# master-sim800-esp32-30pin.net
KiCad netlist of a schematic drawn in EAGLE
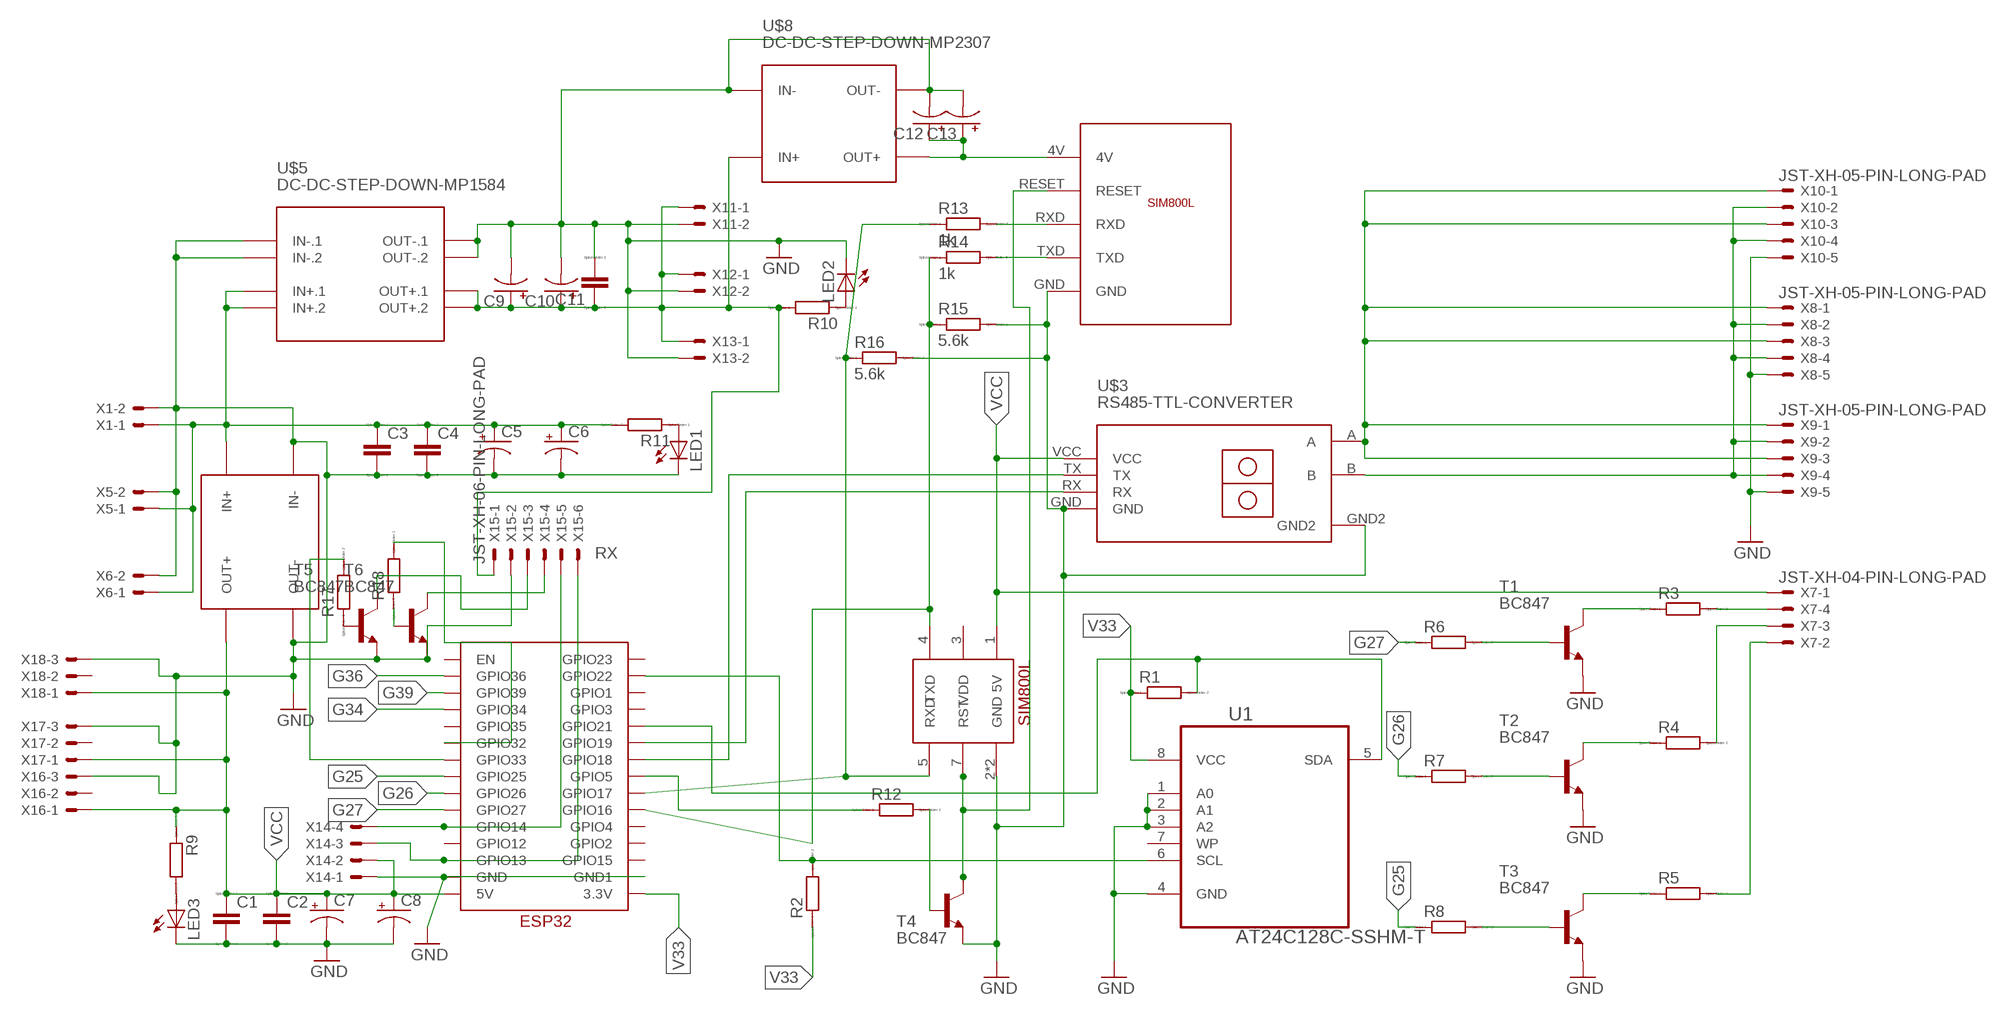
[diagram p0: schematic, sheet 1]

(export (version "E")
  (design (tool "Eeschema 10.0.6"))
  (components
    (comp (ref "C1") (value "C") (footprint "eagle-import:C0805") (libsource (lib "eagle-import") (part "C")))
    (comp (ref "C2") (value "C") (footprint "eagle-import:C0805") (libsource (lib "eagle-import") (part "C")))
    (comp (ref "C3") (value "C") (footprint "eagle-import:C0805") (libsource (lib "eagle-import") (part "C")))
    (comp (ref "C4") (value "C") (footprint "eagle-import:C0805") (libsource (lib "eagle-import") (part "C")))
    (comp (ref "C5")
      (value "CPOL-USE5-8.5")
      (footprint "eagle-import:E5-8,5")
      (libsource (lib "eagle-import") (part "CPOL-USE5-8.5"))
    )
    (comp (ref "C6")
      (value "CPOL-USE5-8.5")
      (footprint "eagle-import:E5-8,5")
      (libsource (lib "eagle-import") (part "CPOL-USE5-8.5"))
    )
    (comp (ref "C7")
      (value "CPOL-USE5-8.5")
      (footprint "eagle-import:E5-8,5")
      (libsource (lib "eagle-import") (part "CPOL-USE5-8.5"))
    )
    (comp (ref "C8")
      (value "CPOL-USE5-8.5")
      (footprint "eagle-import:E5-8,5")
      (libsource (lib "eagle-import") (part "CPOL-USE5-8.5"))
    )
    (comp (ref "C9")
      (value "CPOL-USE5-6")
      (footprint "eagle-import:E5-6")
      (libsource (lib "eagle-import") (part "CPOL-USE5-6"))
    )
    (comp (ref "C10")
      (value "CPOL-USE5-6")
      (footprint "eagle-import:E5-6")
      (libsource (lib "eagle-import") (part "CPOL-USE5-6"))
    )
    (comp (ref "C11")
      (value "C")
      (footprint "eagle-import:C0805")
      (libsource (lib "eagle-import") (part "C"))
    )
    (comp (ref "C12")
      (value "CPOL-USE5-8.5")
      (footprint "eagle-import:E5-8,5")
      (libsource (lib "eagle-import") (part "CPOL-USE5-8.5"))
    )
    (comp (ref "C13")
      (value "CPOL-USE5-8.5")
      (footprint "eagle-import:E5-8,5")
      (libsource (lib "eagle-import") (part "CPOL-USE5-8.5"))
    )
    (comp (ref "LED1")
      (value "LEDCHIPLED_1206")
      (footprint "eagle-import:CHIPLED_1206")
      (libsource (lib "eagle-import") (part "LEDCHIPLED_1206"))
    )
    (comp (ref "LED2")
      (value "LEDCHIPLED_1206")
      (footprint "eagle-import:CHIPLED_1206")
      (libsource (lib "eagle-import") (part "LEDCHIPLED_1206"))
    )
    (comp (ref "LED3")
      (value "LEDCHIPLED_1206")
      (footprint "eagle-import:CHIPLED_1206")
      (libsource (lib "eagle-import") (part "LEDCHIPLED_1206"))
    )
    (comp (ref "R1")
      (value "RR1206")
      (footprint "eagle-import:R1206")
      (libsource (lib "eagle-import") (part "RR1206"))
    )
    (comp (ref "R2")
      (value "RR1206")
      (footprint "eagle-import:R1206")
      (libsource (lib "eagle-import") (part "RR1206"))
    )
    (comp (ref "R3")
      (value "RR1206")
      (footprint "eagle-import:R1206")
      (libsource (lib "eagle-import") (part "RR1206"))
    )
    (comp (ref "R4")
      (value "RR1206")
      (footprint "eagle-import:R1206")
      (libsource (lib "eagle-import") (part "RR1206"))
    )
    (comp (ref "R5")
      (value "RR1206")
      (footprint "eagle-import:R1206")
      (libsource (lib "eagle-import") (part "RR1206"))
    )
    (comp (ref "R6")
      (value "RR1206")
      (footprint "eagle-import:R1206")
      (libsource (lib "eagle-import") (part "RR1206"))
    )
    (comp (ref "R7")
      (value "RR1206")
      (footprint "eagle-import:R1206")
      (libsource (lib "eagle-import") (part "RR1206"))
    )
    (comp (ref "R8")
      (value "RR1206")
      (footprint "eagle-import:R1206")
      (libsource (lib "eagle-import") (part "RR1206"))
    )
    (comp (ref "R9")
      (value "RR1206")
      (footprint "eagle-import:R1206")
      (libsource (lib "eagle-import") (part "RR1206"))
    )
    (comp (ref "R10")
      (value "RR1206")
      (footprint "eagle-import:R1206")
      (libsource (lib "eagle-import") (part "RR1206"))
    )
    (comp (ref "R11")
      (value "RR1206")
      (footprint "eagle-import:R1206")
      (libsource (lib "eagle-import") (part "RR1206"))
    )
    (comp (ref "R12")
      (value "RR1206")
      (footprint "eagle-import:R1206")
      (libsource (lib "eagle-import") (part "RR1206"))
    )
    (comp (ref "R13")
      (value "1k")
      (footprint "eagle-import:R1206")
      (libsource (lib "eagle-import") (part "RR1206"))
    )
    (comp (ref "R14")
      (value "1k")
      (footprint "eagle-import:R1206")
      (libsource (lib "eagle-import") (part "RR1206"))
    )
    (comp (ref "R15")
      (value "5.6k")
      (footprint "eagle-import:R1206")
      (libsource (lib "eagle-import") (part "RR1206"))
    )
    (comp (ref "R16")
      (value "5.6k")
      (footprint "eagle-import:R1206")
      (libsource (lib "eagle-import") (part "RR1206"))
    )
    (comp (ref "R17")
      (value "RR1206")
      (footprint "eagle-import:R1206")
      (libsource (lib "eagle-import") (part "RR1206"))
    )
    (comp (ref "R18")
      (value "RR1206")
      (footprint "eagle-import:R1206")
      (libsource (lib "eagle-import") (part "RR1206"))
    )
    (comp (ref "T1")
      (value "BC847")
      (footprint "eagle-import:SOT23")
      (libsource (lib "eagle-import") (part "BC847"))
    )
    (comp (ref "T2")
      (value "BC847")
      (footprint "eagle-import:SOT23")
      (libsource (lib "eagle-import") (part "BC847"))
    )
    (comp (ref "T3")
      (value "BC847")
      (footprint "eagle-import:SOT23")
      (libsource (lib "eagle-import") (part "BC847"))
    )
    (comp (ref "T4")
      (value "BC847")
      (footprint "eagle-import:SOT23")
      (libsource (lib "eagle-import") (part "BC847"))
    )
    (comp (ref "T5")
      (value "BC847")
      (footprint "eagle-import:SOT23")
      (libsource (lib "eagle-import") (part "BC847"))
    )
    (comp (ref "T6")
      (value "BC847")
      (footprint "eagle-import:SOT23")
      (libsource (lib "eagle-import") (part "BC847"))
    )
    (comp (ref "U$1")
      (value "ESP32-30PIN")
      (footprint "eagle-import:ESP32-30PIN")
      (libsource (lib "eagle-import") (part "ESP32-30PIN"))
    )
    (comp (ref "U$2")
      (value "SIM800L")
      (footprint "eagle-import:SIP")
      (libsource (lib "eagle-import") (part "SIM800L"))
    )
    (comp (ref "U$3")
      (value "RS485-TTL-CONVERTER")
      (footprint "eagle-import:RS485-TTL-CONVERTER")
      (libsource (lib "eagle-import") (part "RS485-TTL-CONVERTER"))
    )
    (comp (ref "U$4")
      (value "DC-DC-STEP-DOWN-MP2307")
      (footprint "eagle-import:DC-DC-STEP-DOWN-MP2307")
      (libsource (lib "eagle-import") (part "DC-DC-STEP-DOWN-MP2307"))
    )
    (comp (ref "U$5")
      (value "DC-DC-STEP-DOWN-MP1584")
      (footprint "eagle-import:DC-DC-STEP-DOWN-MP1584")
      (libsource (lib "eagle-import") (part "DC-DC-STEP-DOWN-MP1584"))
    )
    (comp (ref "U$7")
      (value "SIM800L-V1")
      (footprint "eagle-import:SIM800L")
      (libsource (lib "eagle-import") (part "SIM800L-V1"))
    )
    (comp (ref "U$8")
      (value "DC-DC-STEP-DOWN-MP2307")
      (footprint "eagle-import:DC-DC-STEP-DOWN-MP2307")
      (libsource (lib "eagle-import") (part "DC-DC-STEP-DOWN-MP2307"))
    )
    (comp (ref "U1")
      (value "AT24C128C-SSHM-T")
      (footprint "eagle-import:SOIC127P600X175-8N")
      (fields (field (name "MF") "Microchip"))
      (libsource (lib "eagle-import") (part "AT24C128C-SSHM-T"))
    )
    (comp (ref "X1")
      (value "JST-XH-02-PIN-LONG-PAD")
      (footprint "eagle-import:JST-XH-02-PACKAGE-LONG-PAD")
      (libsource (lib "eagle-import") (part "JST-XH-02-PIN-LONG-PAD"))
    )
    (comp (ref "X5")
      (value "JST-XH-02-PIN-LONG-PAD")
      (footprint "eagle-import:JST-XH-02-PACKAGE-LONG-PAD")
      (libsource (lib "eagle-import") (part "JST-XH-02-PIN-LONG-PAD"))
    )
    (comp (ref "X6")
      (value "JST-XH-02-PIN-LONG-PAD")
      (footprint "eagle-import:JST-XH-02-PACKAGE-LONG-PAD")
      (libsource (lib "eagle-import") (part "JST-XH-02-PIN-LONG-PAD"))
    )
    (comp (ref "X7")
      (value "JST-XH-04-PIN-LONG-PAD")
      (footprint "eagle-import:JST-XH-04-PACKAGE-LONG-PAD")
      (libsource (lib "eagle-import") (part "JST-XH-04-PIN-LONG-PAD"))
    )
    (comp (ref "X8")
      (value "JST-XH-05-PIN-LONG-PAD")
      (footprint "eagle-import:JST-XH-05-PACKAGE-LONG-PAD")
      (libsource (lib "eagle-import") (part "JST-XH-05-PIN-LONG-PAD"))
    )
    (comp (ref "X9")
      (value "JST-XH-05-PIN-LONG-PAD")
      (footprint "eagle-import:JST-XH-05-PACKAGE-LONG-PAD")
      (libsource (lib "eagle-import") (part "JST-XH-05-PIN-LONG-PAD"))
    )
    (comp (ref "X10")
      (value "JST-XH-05-PIN-LONG-PAD")
      (footprint "eagle-import:JST-XH-05-PACKAGE-LONG-PAD")
      (libsource (lib "eagle-import") (part "JST-XH-05-PIN-LONG-PAD"))
    )
    (comp (ref "X11")
      (value "JST-XH-02-PIN-LONG-PAD")
      (footprint "eagle-import:JST-XH-02-PACKAGE-LONG-PAD")
      (libsource (lib "eagle-import") (part "JST-XH-02-PIN-LONG-PAD"))
    )
    (comp (ref "X12")
      (value "JST-XH-02-PIN-LONG-PAD")
      (footprint "eagle-import:JST-XH-02-PACKAGE-LONG-PAD")
      (libsource (lib "eagle-import") (part "JST-XH-02-PIN-LONG-PAD"))
    )
    (comp (ref "X13")
      (value "JST-XH-02-PIN-LONG-PAD")
      (footprint "eagle-import:JST-XH-02-PACKAGE-LONG-PAD")
      (libsource (lib "eagle-import") (part "JST-XH-02-PIN-LONG-PAD"))
    )
    (comp (ref "X14")
      (value "JST-XH-04-PIN-LONG-PAD")
      (footprint "eagle-import:JST-XH-04-PACKAGE-LONG-PAD")
      (libsource (lib "eagle-import") (part "JST-XH-04-PIN-LONG-PAD"))
    )
    (comp (ref "X15")
      (value "JST-XH-06-PIN-LONG-PAD")
      (footprint "eagle-import:JST-XH-06-PACKAGE-LONG-PAD")
      (libsource (lib "eagle-import") (part "JST-XH-06-PIN-LONG-PAD"))
    )
    (comp (ref "X16")
      (value "JST-XH-03-PIN-LONG-PAD")
      (footprint "eagle-import:JST-XH-03-PACKAGE-LONG-PAD")
      (libsource (lib "eagle-import") (part "JST-XH-03-PIN-LONG-PAD"))
    )
    (comp (ref "X17")
      (value "JST-XH-03-PIN-LONG-PAD")
      (footprint "eagle-import:JST-XH-03-PACKAGE-LONG-PAD")
      (libsource (lib "eagle-import") (part "JST-XH-03-PIN-LONG-PAD"))
    )
    (comp (ref "X18")
      (value "JST-XH-03-PIN-LONG-PAD")
      (footprint "eagle-import:JST-XH-03-PACKAGE-LONG-PAD")
      (libsource (lib "eagle-import") (part "JST-XH-03-PIN-LONG-PAD"))
    )
  )
  (nets
    (net (code "1") (name "G25") (class "Default")
      (node (ref "R8") (pin "1") (pinfunction "1_1") (pintype "passive"))
      (node (ref "U$1") (pin "GPIO25") (pinfunction "GPIO25_GPIO25") (pintype "bidirectional"))
    )
    (net (code "2") (name "G26") (class "Default")
      (node (ref "R7") (pin "1") (pinfunction "1_1") (pintype "passive"))
      (node (ref "U$1") (pin "GPIO26") (pinfunction "GPIO26_GPIO26") (pintype "bidirectional"))
    )
    (net (code "3") (name "G27") (class "Default")
      (node (ref "R6") (pin "1") (pinfunction "1_1") (pintype "passive"))
      (node (ref "U$1") (pin "GPIO27") (pinfunction "GPIO27_GPIO27") (pintype "bidirectional"))
    )
    (net (code "4") (name "G34") (class "Default")
      (node (ref "U$1") (pin "GPIO34") (pinfunction "GPIO34_GPIO34") (pintype "bidirectional"))
    )
    (net (code "5") (name "G36") (class "Default")
      (node (ref "U$1") (pin "GPIO36") (pinfunction "GPIO36_GPIO36") (pintype "bidirectional"))
    )
    (net (code "6") (name "G39") (class "Default")
      (node (ref "U$1") (pin "GPIO39") (pinfunction "GPIO39_GPIO39") (pintype "bidirectional"))
    )
    (net (code "7") (name "GND") (class "Default")
      (node (ref "C1") (pin "2") (pinfunction "2_2") (pintype "passive"))
      (node (ref "C10") (pin "-") (pinfunction "-_-") (pintype "passive"))
      (node (ref "C11") (pin "2") (pinfunction "2_2") (pintype "passive"))
      (node (ref "C12") (pin "-") (pinfunction "-_-") (pintype "passive"))
      (node (ref "C13") (pin "-") (pinfunction "-_-") (pintype "passive"))
      (node (ref "C2") (pin "2") (pinfunction "2_2") (pintype "passive"))
      (node (ref "C3") (pin "2") (pinfunction "2_2") (pintype "passive"))
      (node (ref "C4") (pin "2") (pinfunction "2_2") (pintype "passive"))
      (node (ref "C5") (pin "-") (pinfunction "-_-") (pintype "passive"))
      (node (ref "C6") (pin "-") (pinfunction "-_-") (pintype "passive"))
      (node (ref "C7") (pin "-") (pinfunction "-_-") (pintype "passive"))
      (node (ref "C8") (pin "-") (pinfunction "-_-") (pintype "passive"))
      (node (ref "C9") (pin "-") (pinfunction "-_-") (pintype "passive"))
      (node (ref "LED1") (pin "C") (pinfunction "C_C") (pintype "passive"))
      (node (ref "LED2") (pin "C") (pinfunction "C_C") (pintype "passive"))
      (node (ref "LED3") (pin "C") (pinfunction "C_C") (pintype "passive"))
      (node (ref "R15") (pin "2") (pinfunction "2_2") (pintype "passive"))
      (node (ref "R16") (pin "2") (pinfunction "2_2") (pintype "passive"))
      (node (ref "T1") (pin "2") (pinfunction "E_2") (pintype "passive"))
      (node (ref "T2") (pin "2") (pinfunction "E_2") (pintype "passive"))
      (node (ref "T3") (pin "2") (pinfunction "E_2") (pintype "passive"))
      (node (ref "T4") (pin "2") (pinfunction "E_2") (pintype "passive"))
      (node (ref "T5") (pin "2") (pinfunction "E_2") (pintype "passive"))
      (node (ref "T6") (pin "2") (pinfunction "E_2") (pintype "passive"))
      (node (ref "U$1") (pin "GND") (pinfunction "GND_GND") (pintype "bidirectional"))
      (node (ref "U$1") (pin "GND1") (pinfunction "GND1_GND1") (pintype "bidirectional"))
      (node (ref "U$2") (pin "2") (pinfunction "GND_2") (pintype "bidirectional"))
      (node (ref "U$2") (pin "6") (pinfunction "GND_6") (pintype "bidirectional"))
      (node (ref "U$3") (pin "GND") (pinfunction "GND_GND") (pintype "passive"))
      (node (ref "U$3") (pin "GND2") (pinfunction "GND2_GND2") (pintype "power_in"))
      (node (ref "U$4") (pin "IN-") (pinfunction "IN-_IN-") (pintype "bidirectional"))
      (node (ref "U$4") (pin "OUT-") (pinfunction "OUT-_OUT-") (pintype "bidirectional"))
      (node (ref "U$5") (pin "IN-.1") (pinfunction "IN-.1_IN-.1") (pintype "bidirectional"))
      (node (ref "U$5") (pin "IN-.2") (pinfunction "IN-.2_IN-.2") (pintype "bidirectional"))
      (node (ref "U$5") (pin "OUT-.1") (pinfunction "OUT-.1_OUT-.1") (pintype "bidirectional"))
      (node (ref "U$5") (pin "OUT-.2") (pinfunction "OUT-.2_OUT-.2") (pintype "bidirectional"))
      (node (ref "U$7") (pin "GND") (pinfunction "GND_GND") (pintype "bidirectional"))
      (node (ref "U$8") (pin "IN-") (pinfunction "IN-_IN-") (pintype "bidirectional"))
      (node (ref "U$8") (pin "OUT-") (pinfunction "OUT-_OUT-") (pintype "bidirectional"))
      (node (ref "U1") (pin "1") (pinfunction "A0_1") (pintype "input"))
      (node (ref "U1") (pin "2") (pinfunction "A1_2") (pintype "input"))
      (node (ref "U1") (pin "3") (pinfunction "A2_3") (pintype "input"))
      (node (ref "U1") (pin "4") (pinfunction "GND_4") (pintype "passive"))
      (node (ref "X1") (pin "2") (pinfunction "S_2") (pintype "passive"))
      (node (ref "X10") (pin "5") (pinfunction "S_5") (pintype "passive"))
      (node (ref "X11") (pin "2") (pinfunction "S_2") (pintype "passive"))
      (node (ref "X12") (pin "2") (pinfunction "S_2") (pintype "passive"))
      (node (ref "X13") (pin "2") (pinfunction "S_2") (pintype "passive"))
      (node (ref "X14") (pin "1") (pinfunction "S_1") (pintype "passive"))
      (node (ref "X15") (pin "2") (pinfunction "S_2") (pintype "passive"))
      (node (ref "X16") (pin "3") (pinfunction "S_3") (pintype "passive"))
      (node (ref "X17") (pin "3") (pinfunction "S_3") (pintype "passive"))
      (node (ref "X18") (pin "3") (pinfunction "S_3") (pintype "passive"))
      (node (ref "X5") (pin "2") (pinfunction "S_2") (pintype "passive"))
      (node (ref "X6") (pin "2") (pinfunction "S_2") (pintype "passive"))
      (node (ref "X8") (pin "5") (pinfunction "S_5") (pintype "passive"))
      (node (ref "X9") (pin "5") (pinfunction "S_5") (pintype "passive"))
    )
    (net (code "8") (name "Net-(C12-Pad+)") (class "Default")
      (node (ref "C12") (pin "+") (pinfunction "+_+") (pintype "passive"))
      (node (ref "C13") (pin "+") (pinfunction "+_+") (pintype "passive"))
      (node (ref "U$7") (pin "4V") (pinfunction "4V_4V") (pintype "bidirectional"))
      (node (ref "U$8") (pin "OUT+") (pinfunction "OUT+_OUT+") (pintype "bidirectional"))
    )
    (net (code "9") (name "Net-(LED1-PadA)") (class "Default")
      (node (ref "LED1") (pin "A") (pinfunction "A_A") (pintype "passive"))
      (node (ref "R11") (pin "1") (pinfunction "1_1") (pintype "passive"))
    )
    (net (code "10") (name "Net-(LED2-PadA)") (class "Default")
      (node (ref "LED2") (pin "A") (pinfunction "A_A") (pintype "passive"))
      (node (ref "R10") (pin "1") (pinfunction "1_1") (pintype "passive"))
    )
    (net (code "11") (name "Net-(LED3-PadA)") (class "Default")
      (node (ref "LED3") (pin "A") (pinfunction "A_A") (pintype "passive"))
      (node (ref "R9") (pin "2") (pinfunction "2_2") (pintype "passive"))
    )
    (net (code "12") (name "Net-(R12-Pad1)") (class "Default")
      (node (ref "R12") (pin "1") (pinfunction "1_1") (pintype "passive"))
      (node (ref "U$1") (pin "GPIO5") (pinfunction "GPIO5_GPIO5") (pintype "bidirectional"))
    )
    (net (code "13") (name "Net-(R13-Pad2)") (class "Default")
      (node (ref "R13") (pin "2") (pinfunction "2_2") (pintype "passive"))
      (node (ref "U$7") (pin "RXD") (pinfunction "RXD_RXD") (pintype "bidirectional"))
    )
    (net (code "14") (name "Net-(R14-Pad2)") (class "Default")
      (node (ref "R14") (pin "2") (pinfunction "2_2") (pintype "passive"))
      (node (ref "U$7") (pin "TXD") (pinfunction "TXD_TXD") (pintype "bidirectional"))
    )
    (net (code "15") (name "Net-(R17-Pad2)") (class "Default")
      (node (ref "R17") (pin "2") (pinfunction "2_2") (pintype "passive"))
      (node (ref "U$1") (pin "GPIO33") (pinfunction "GPIO33_GPIO33") (pintype "bidirectional"))
    )
    (net (code "16") (name "Net-(R18-Pad2)") (class "Default")
      (node (ref "R18") (pin "2") (pinfunction "2_2") (pintype "passive"))
      (node (ref "U$1") (pin "GPIO32") (pinfunction "GPIO32_GPIO32") (pintype "bidirectional"))
    )
    (net (code "17") (name "Net-(T1-B)") (class "Default")
      (node (ref "R6") (pin "2") (pinfunction "2_2") (pintype "passive"))
      (node (ref "T1") (pin "1") (pinfunction "B_1") (pintype "passive"))
    )
    (net (code "18") (name "Net-(T1-C)") (class "Default")
      (node (ref "R3") (pin "1") (pinfunction "1_1") (pintype "passive"))
      (node (ref "T1") (pin "3") (pinfunction "C_3") (pintype "passive"))
    )
    (net (code "19") (name "Net-(T2-B)") (class "Default")
      (node (ref "R7") (pin "2") (pinfunction "2_2") (pintype "passive"))
      (node (ref "T2") (pin "1") (pinfunction "B_1") (pintype "passive"))
    )
    (net (code "20") (name "Net-(T2-C)") (class "Default")
      (node (ref "R4") (pin "1") (pinfunction "1_1") (pintype "passive"))
      (node (ref "T2") (pin "3") (pinfunction "C_3") (pintype "passive"))
    )
    (net (code "21") (name "Net-(T3-B)") (class "Default")
      (node (ref "R8") (pin "2") (pinfunction "2_2") (pintype "passive"))
      (node (ref "T3") (pin "1") (pinfunction "B_1") (pintype "passive"))
    )
    (net (code "22") (name "Net-(T3-C)") (class "Default")
      (node (ref "R5") (pin "1") (pinfunction "1_1") (pintype "passive"))
      (node (ref "T3") (pin "3") (pinfunction "C_3") (pintype "passive"))
    )
    (net (code "23") (name "Net-(T4-B)") (class "Default")
      (node (ref "R12") (pin "2") (pinfunction "2_2") (pintype "passive"))
      (node (ref "T4") (pin "1") (pinfunction "B_1") (pintype "passive"))
    )
    (net (code "24") (name "Net-(T4-C)") (class "Default")
      (node (ref "T4") (pin "3") (pinfunction "C_3") (pintype "passive"))
      (node (ref "U$2") (pin "7") (pinfunction "RST_7") (pintype "bidirectional"))
      (node (ref "U$7") (pin "RESET") (pinfunction "RESET_RESET") (pintype "bidirectional"))
    )
    (net (code "25") (name "Net-(T5-B)") (class "Default")
      (node (ref "R17") (pin "1") (pinfunction "1_1") (pintype "passive"))
      (node (ref "T5") (pin "1") (pinfunction "B_1") (pintype "passive"))
    )
    (net (code "26") (name "Net-(T5-C)") (class "Default")
      (node (ref "T5") (pin "3") (pinfunction "C_3") (pintype "passive"))
      (node (ref "X15") (pin "3") (pinfunction "S_3") (pintype "passive"))
    )
    (net (code "27") (name "Net-(T6-B)") (class "Default")
      (node (ref "R18") (pin "1") (pinfunction "1_1") (pintype "passive"))
      (node (ref "T6") (pin "1") (pinfunction "B_1") (pintype "passive"))
    )
    (net (code "28") (name "Net-(T6-C)") (class "Default")
      (node (ref "T6") (pin "3") (pinfunction "C_3") (pintype "passive"))
      (node (ref "X15") (pin "4") (pinfunction "S_4") (pintype "passive"))
    )
    (net (code "29") (name "Net-(U$1-PadGPIO18)") (class "Default")
      (node (ref "U$1") (pin "GPIO18") (pinfunction "GPIO18_GPIO18") (pintype "bidirectional"))
      (node (ref "U$3") (pin "TX") (pinfunction "TX_TX") (pintype "passive"))
    )
    (net (code "30") (name "Net-(U$1-PadGPIO19)") (class "Default")
      (node (ref "U$1") (pin "GPIO19") (pinfunction "GPIO19_GPIO19") (pintype "bidirectional"))
      (node (ref "U$3") (pin "RX") (pinfunction "RX_RX") (pintype "passive"))
    )
    (net (code "31") (name "Net-(U$2-RXD)") (class "Default")
      (node (ref "R13") (pin "1") (pinfunction "1_1") (pintype "passive"))
      (node (ref "R16") (pin "1") (pinfunction "1_1") (pintype "passive"))
      (node (ref "U$1") (pin "GPIO17") (pinfunction "GPIO17_GPIO17") (pintype "bidirectional"))
      (node (ref "U$2") (pin "5") (pinfunction "RXD_5") (pintype "bidirectional"))
    )
    (net (code "32") (name "Net-(U$2-TXD)") (class "Default")
      (node (ref "R14") (pin "1") (pinfunction "1_1") (pintype "passive"))
      (node (ref "R15") (pin "1") (pinfunction "1_1") (pintype "passive"))
      (node (ref "U$1") (pin "GPIO16") (pinfunction "GPIO16_GPIO16") (pintype "bidirectional"))
      (node (ref "U$2") (pin "4") (pinfunction "TXD_4") (pintype "bidirectional"))
    )
    (net (code "33") (name "Net-(U1-SCL)") (class "Default")
      (node (ref "R2") (pin "2") (pinfunction "2_2") (pintype "passive"))
      (node (ref "U$1") (pin "GPIO22") (pinfunction "GPIO22_GPIO22") (pintype "bidirectional"))
      (node (ref "U1") (pin "6") (pinfunction "SCL_6") (pintype "input"))
    )
    (net (code "34") (name "Net-(U1-SDA)") (class "Default")
      (node (ref "R1") (pin "2") (pinfunction "2_2") (pintype "passive"))
      (node (ref "U$1") (pin "GPIO21") (pinfunction "GPIO21_GPIO21") (pintype "bidirectional"))
      (node (ref "U1") (pin "5") (pinfunction "SDA_5") (pintype "bidirectional"))
    )
    (net (code "35") (name "Net-(X1A-S)") (class "Default")
      (node (ref "C3") (pin "1") (pinfunction "1_1") (pintype "passive"))
      (node (ref "C4") (pin "1") (pinfunction "1_1") (pintype "passive"))
      (node (ref "C5") (pin "+") (pinfunction "+_+") (pintype "passive"))
      (node (ref "C6") (pin "+") (pinfunction "+_+") (pintype "passive"))
      (node (ref "R11") (pin "2") (pinfunction "2_2") (pintype "passive"))
      (node (ref "U$4") (pin "IN+") (pinfunction "IN+_IN+") (pintype "bidirectional"))
      (node (ref "U$5") (pin "IN+.1") (pinfunction "IN+.1_IN+.1") (pintype "bidirectional"))
      (node (ref "U$5") (pin "IN+.2") (pinfunction "IN+.2_IN+.2") (pintype "bidirectional"))
      (node (ref "X1") (pin "1") (pinfunction "S_1") (pintype "passive"))
      (node (ref "X5") (pin "1") (pinfunction "S_1") (pintype "passive"))
      (node (ref "X6") (pin "1") (pinfunction "S_1") (pintype "passive"))
    )
    (net (code "36") (name "Net-(X7B-S)") (class "Default")
      (node (ref "R5") (pin "2") (pinfunction "2_2") (pintype "passive"))
      (node (ref "X7") (pin "2") (pinfunction "S_2") (pintype "passive"))
    )
    (net (code "37") (name "Net-(X7C-S)") (class "Default")
      (node (ref "R4") (pin "2") (pinfunction "2_2") (pintype "passive"))
      (node (ref "X7") (pin "3") (pinfunction "S_3") (pintype "passive"))
    )
    (net (code "38") (name "Net-(X7D-S)") (class "Default")
      (node (ref "R3") (pin "2") (pinfunction "2_2") (pintype "passive"))
      (node (ref "X7") (pin "4") (pinfunction "S_4") (pintype "passive"))
    )
    (net (code "39") (name "Net-(X10A-S)") (class "Default")
      (node (ref "U$3") (pin "A") (pinfunction "A_A") (pintype "passive"))
      (node (ref "X10") (pin "1") (pinfunction "S_1") (pintype "passive"))
      (node (ref "X10") (pin "3") (pinfunction "S_3") (pintype "passive"))
      (node (ref "X8") (pin "1") (pinfunction "S_1") (pintype "passive"))
      (node (ref "X8") (pin "3") (pinfunction "S_3") (pintype "passive"))
      (node (ref "X9") (pin "1") (pinfunction "S_1") (pintype "passive"))
      (node (ref "X9") (pin "3") (pinfunction "S_3") (pintype "passive"))
    )
    (net (code "40") (name "Net-(X10B-S)") (class "Default")
      (node (ref "U$3") (pin "B") (pinfunction "B_B") (pintype "passive"))
      (node (ref "X10") (pin "2") (pinfunction "S_2") (pintype "passive"))
      (node (ref "X10") (pin "4") (pinfunction "S_4") (pintype "passive"))
      (node (ref "X8") (pin "2") (pinfunction "S_2") (pintype "passive"))
      (node (ref "X8") (pin "4") (pinfunction "S_4") (pintype "passive"))
      (node (ref "X9") (pin "2") (pinfunction "S_2") (pintype "passive"))
      (node (ref "X9") (pin "4") (pinfunction "S_4") (pintype "passive"))
    )
    (net (code "41") (name "Net-(X11A-S)") (class "Default")
      (node (ref "C10") (pin "+") (pinfunction "+_+") (pintype "passive"))
      (node (ref "C11") (pin "1") (pinfunction "1_1") (pintype "passive"))
      (node (ref "C9") (pin "+") (pinfunction "+_+") (pintype "passive"))
      (node (ref "R10") (pin "2") (pinfunction "2_2") (pintype "passive"))
      (node (ref "U$5") (pin "OUT+.1") (pinfunction "OUT+.1_OUT+.1") (pintype "bidirectional"))
      (node (ref "U$5") (pin "OUT+.2") (pinfunction "OUT+.2_OUT+.2") (pintype "bidirectional"))
      (node (ref "U$8") (pin "IN+") (pinfunction "IN+_IN+") (pintype "bidirectional"))
      (node (ref "X11") (pin "1") (pinfunction "S_1") (pintype "passive"))
      (node (ref "X12") (pin "1") (pinfunction "S_1") (pintype "passive"))
      (node (ref "X13") (pin "1") (pinfunction "S_1") (pintype "passive"))
      (node (ref "X15") (pin "1") (pinfunction "S_1") (pintype "passive"))
    )
    (net (code "42") (name "Net-(X14C-S)") (class "Default")
      (node (ref "U$1") (pin "GPIO13") (pinfunction "GPIO13_GPIO13") (pintype "bidirectional"))
      (node (ref "X14") (pin "3") (pinfunction "S_3") (pintype "passive"))
      (node (ref "X15") (pin "6") (pinfunction "S_6") (pintype "passive"))
    )
    (net (code "43") (name "Net-(X14D-S)") (class "Default")
      (node (ref "U$1") (pin "GPIO14") (pinfunction "GPIO14_GPIO14") (pintype "bidirectional"))
      (node (ref "X14") (pin "4") (pinfunction "S_4") (pintype "passive"))
      (node (ref "X15") (pin "5") (pinfunction "S_5") (pintype "passive"))
    )
    (net (code "44") (name "V33") (class "Default")
      (node (ref "R1") (pin "1") (pinfunction "1_1") (pintype "passive"))
      (node (ref "R2") (pin "1") (pinfunction "1_1") (pintype "passive"))
      (node (ref "U$1") (pin "3.3V") (pinfunction "3.3V_3.3V") (pintype "bidirectional"))
      (node (ref "U1") (pin "8") (pinfunction "VCC_8") (pintype "power_in"))
    )
    (net (code "45") (name "VCC") (class "Default")
      (node (ref "C1") (pin "1") (pinfunction "1_1") (pintype "passive"))
      (node (ref "C2") (pin "1") (pinfunction "1_1") (pintype "passive"))
      (node (ref "C7") (pin "+") (pinfunction "+_+") (pintype "passive"))
      (node (ref "C8") (pin "+") (pinfunction "+_+") (pintype "passive"))
      (node (ref "R9") (pin "1") (pinfunction "1_1") (pintype "passive"))
      (node (ref "U$1") (pin "5V") (pinfunction "5V_5V") (pintype "bidirectional"))
      (node (ref "U$2") (pin "1") (pinfunction "5V_1") (pintype "bidirectional"))
      (node (ref "U$3") (pin "VCC") (pinfunction "VCC_VCC") (pintype "passive"))
      (node (ref "U$4") (pin "OUT+") (pinfunction "OUT+_OUT+") (pintype "bidirectional"))
      (node (ref "X14") (pin "2") (pinfunction "S_2") (pintype "passive"))
      (node (ref "X16") (pin "1") (pinfunction "S_1") (pintype "passive"))
      (node (ref "X17") (pin "1") (pinfunction "S_1") (pintype "passive"))
      (node (ref "X18") (pin "1") (pinfunction "S_1") (pintype "passive"))
      (node (ref "X7") (pin "1") (pinfunction "S_1") (pintype "passive"))
    )
    (net (code "46") (name "unconnected-(U$1-PadEN)") (class "Default")
      (node (ref "U$1") (pin "EN") (pinfunction "EN_EN") (pintype "bidirectional"))
    )
    (net (code "47") (name "unconnected-(U$1-PadGPIO1)") (class "Default")
      (node (ref "U$1") (pin "GPIO1") (pinfunction "GPIO1_GPIO1") (pintype "bidirectional"))
    )
    (net (code "48") (name "unconnected-(U$1-PadGPIO2)") (class "Default")
      (node (ref "U$1") (pin "GPIO2") (pinfunction "GPIO2_GPIO2") (pintype "bidirectional"))
    )
    (net (code "49") (name "unconnected-(U$1-PadGPIO3)") (class "Default")
      (node (ref "U$1") (pin "GPIO3") (pinfunction "GPIO3_GPIO3") (pintype "bidirectional"))
    )
    (net (code "50") (name "unconnected-(U$1-PadGPIO4)") (class "Default")
      (node (ref "U$1") (pin "GPIO4") (pinfunction "GPIO4_GPIO4") (pintype "bidirectional"))
    )
    (net (code "51") (name "unconnected-(U$1-PadGPIO12)") (class "Default")
      (node (ref "U$1") (pin "GPIO12") (pinfunction "GPIO12_GPIO12") (pintype "bidirectional"))
    )
    (net (code "52") (name "unconnected-(U$1-PadGPIO15)") (class "Default")
      (node (ref "U$1") (pin "GPIO15") (pinfunction "GPIO15_GPIO15") (pintype "bidirectional"))
    )
    (net (code "53") (name "unconnected-(U$1-PadGPIO23)") (class "Default")
      (node (ref "U$1") (pin "GPIO23") (pinfunction "GPIO23_GPIO23") (pintype "bidirectional"))
    )
    (net (code "54") (name "unconnected-(U$1-PadGPIO35)") (class "Default")
      (node (ref "U$1") (pin "GPIO35") (pinfunction "GPIO35_GPIO35") (pintype "bidirectional"))
    )
    (net (code "55") (name "unconnected-(U$2-VDD-Pad3)") (class "Default")
      (node (ref "U$2") (pin "3") (pinfunction "VDD_3") (pintype "bidirectional"))
    )
    (net (code "56") (name "unconnected-(U1-WP-Pad7)") (class "Default")
      (node (ref "U1") (pin "7") (pinfunction "WP_7") (pintype "input"))
    )
    (net (code "57") (name "unconnected-(X16B-S-Pad2)") (class "Default")
      (node (ref "X16") (pin "2") (pinfunction "S_2") (pintype "passive"))
    )
    (net (code "58") (name "unconnected-(X17B-S-Pad2)") (class "Default")
      (node (ref "X17") (pin "2") (pinfunction "S_2") (pintype "passive"))
    )
    (net (code "59") (name "unconnected-(X18B-S-Pad2)") (class "Default")
      (node (ref "X18") (pin "2") (pinfunction "S_2") (pintype "passive"))
    )
  )
)
